# TurntableStrobeModule.net
KiCad netlist of a schematic drawn in EAGLE
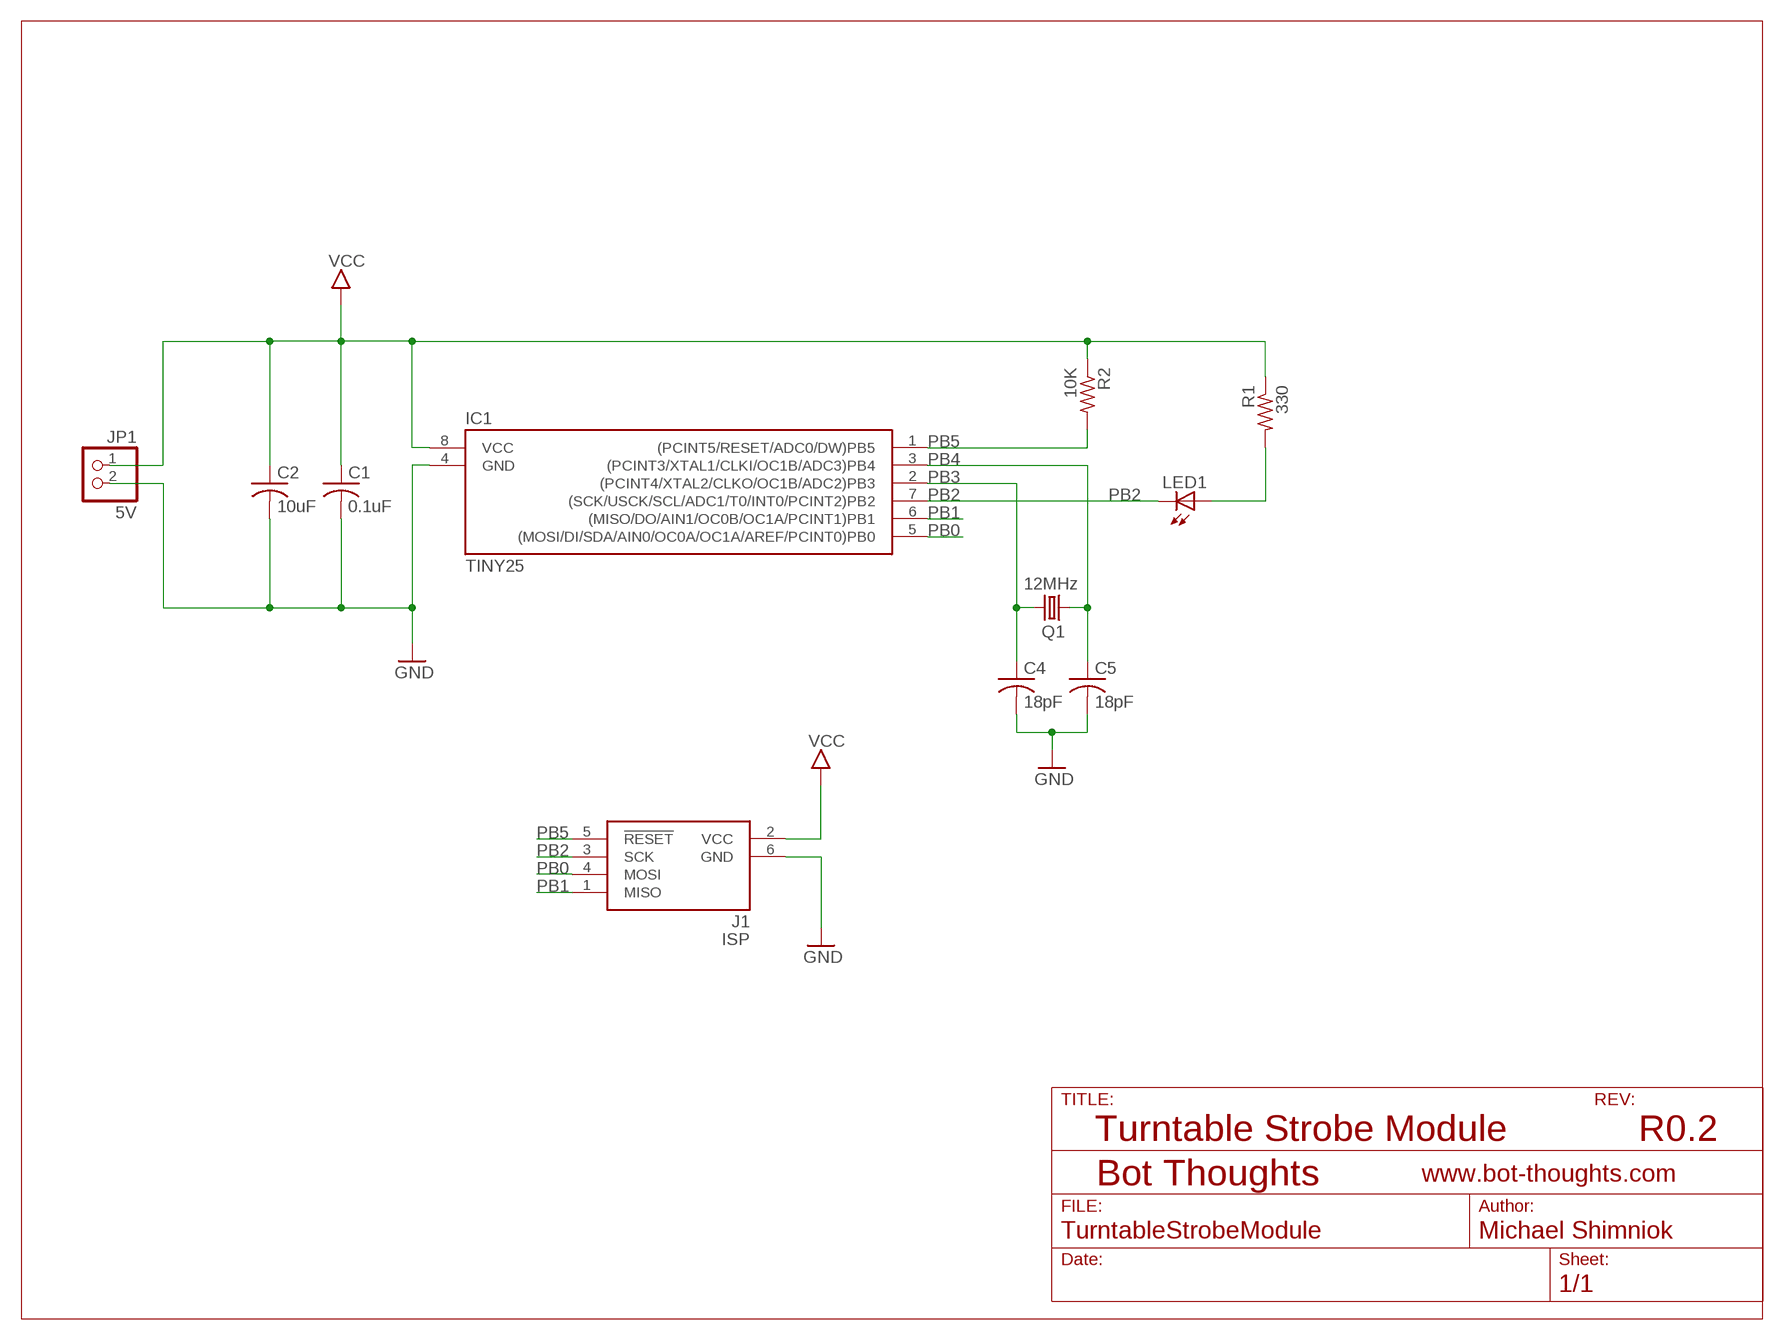
[diagram p0: schematic, sheet 1]

(export (version "E")
  (design (tool "Eeschema 10.0.6"))
  (components
    (comp (ref "C1")
      (value "0.1uF")
      (footprint "eagle-import:C0603")
      (libsource (lib "eagle-import") (part "C-USC0603"))
    )
    (comp (ref "C2")
      (value "10uF")
      (footprint "eagle-import:C1206")
      (libsource (lib "eagle-import") (part "C-USC1206"))
    )
    (comp (ref "C4")
      (value "18pF")
      (footprint "eagle-import:C0603")
      (libsource (lib "eagle-import") (part "C-USC0603"))
    )
    (comp (ref "C5")
      (value "18pF")
      (footprint "eagle-import:C0603")
      (libsource (lib "eagle-import") (part "C-USC0603"))
    )
    (comp (ref "IC1")
      (value "TINY25")
      (footprint "eagle-import:SOIC8N")
      (libsource (lib "eagle-import") (part "TINY25/45/85-20SSU"))
    )
    (comp (ref "J1")
      (value "ISP")
      (footprint "eagle-import:CON6P2R")
      (libsource (lib "eagle-import") (part "AVRISP6_COMPACT"))
    )
    (comp (ref "JP1")
      (value "5V")
      (footprint "eagle-import:1X02-S")
      (libsource (lib "eagle-import") (part "PINHD-1X02_2.54-S"))
    )
    (comp (ref "LED1")
      (value "LED5MMRA")
      (footprint "eagle-import:LED5MMRA")
      (libsource (lib "eagle-import") (part "LED5MMRA"))
    )
    (comp (ref "Q1")
      (value "12MHz")
      (footprint "eagle-import:NDK_2PAD_5X3")
      (libsource (lib "eagle-import") (part "CRYSTALNDK5X3"))
    )
    (comp (ref "R1")
      (value "330")
      (footprint "eagle-import:R0603")
      (libsource (lib "eagle-import") (part "R-US_R0603"))
    )
    (comp (ref "R2")
      (value "10K")
      (footprint "eagle-import:R0603")
      (libsource (lib "eagle-import") (part "R-US_R0603"))
    )
  )
  (nets
    (net (code "1") (name "/PB0") (class "Default")
      (node (ref "IC1") (pin "5") (pinfunction "(MOSI/DI/SDA/AIN0/OC0A/OC1A/AREF/PCINT0)PB0_5") (pintype "bidirectional"))
      (node (ref "J1") (pin "4") (pinfunction "MOSI_4") (pintype "output"))
    )
    (net (code "2") (name "/PB1") (class "Default")
      (node (ref "IC1") (pin "6") (pinfunction "(MISO/DO/AIN1/OC0B/OC1A/PCINT1)PB1_6") (pintype "bidirectional"))
      (node (ref "J1") (pin "1") (pinfunction "MISO_1") (pintype "input"))
    )
    (net (code "3") (name "/PB2") (class "Default")
      (node (ref "IC1") (pin "7") (pinfunction "(SCK/USCK/SCL/ADC1/T0/INT0/PCINT2)PB2_7") (pintype "bidirectional"))
      (node (ref "J1") (pin "3") (pinfunction "SCK_3") (pintype "output"))
      (node (ref "LED1") (pin "C") (pinfunction "C_C") (pintype "passive"))
    )
    (net (code "4") (name "/PB3") (class "Default")
      (node (ref "C4") (pin "1") (pinfunction "1_1") (pintype "passive"))
      (node (ref "IC1") (pin "2") (pinfunction "(PCINT4/XTAL2/CLKO/OC1B/ADC2)PB3_2") (pintype "bidirectional"))
      (node (ref "Q1") (pin "P$2") (pinfunction "2_P$2") (pintype "passive"))
    )
    (net (code "5") (name "/PB4") (class "Default")
      (node (ref "C5") (pin "1") (pinfunction "1_1") (pintype "passive"))
      (node (ref "IC1") (pin "3") (pinfunction "(PCINT3/XTAL1/CLKI/OC1B/ADC3)PB4_3") (pintype "bidirectional"))
      (node (ref "Q1") (pin "P$1") (pinfunction "1_P$1") (pintype "passive"))
    )
    (net (code "6") (name "/PB5") (class "Default")
      (node (ref "IC1") (pin "1") (pinfunction "(PCINT5/RESET/ADC0/DW)PB5_1") (pintype "bidirectional"))
      (node (ref "J1") (pin "5") (pinfunction "~{RESET}_5") (pintype "output"))
      (node (ref "R2") (pin "2") (pinfunction "2_2") (pintype "passive"))
    )
    (net (code "7") (name "GND") (class "Default")
      (node (ref "C1") (pin "2") (pinfunction "2_2") (pintype "passive"))
      (node (ref "C2") (pin "2") (pinfunction "2_2") (pintype "passive"))
      (node (ref "C4") (pin "2") (pinfunction "2_2") (pintype "passive"))
      (node (ref "C5") (pin "2") (pinfunction "2_2") (pintype "passive"))
      (node (ref "IC1") (pin "4") (pinfunction "GND_4") (pintype "power_in"))
      (node (ref "J1") (pin "6") (pinfunction "GND_6") (pintype "power_in"))
      (node (ref "JP1") (pin "2") (pinfunction "2_2") (pintype "passive"))
    )
    (net (code "8") (name "Net-(LED1-PadA)") (class "Default")
      (node (ref "LED1") (pin "A") (pinfunction "A_A") (pintype "passive"))
      (node (ref "R1") (pin "2") (pinfunction "2_2") (pintype "passive"))
    )
    (net (code "9") (name "VCC") (class "Default")
      (node (ref "C1") (pin "1") (pinfunction "1_1") (pintype "passive"))
      (node (ref "C2") (pin "1") (pinfunction "1_1") (pintype "passive"))
      (node (ref "IC1") (pin "8") (pinfunction "VCC_8") (pintype "power_in"))
      (node (ref "J1") (pin "2") (pinfunction "VCC_2") (pintype "power_in"))
      (node (ref "JP1") (pin "1") (pinfunction "1_1") (pintype "passive"))
      (node (ref "R1") (pin "1") (pinfunction "1_1") (pintype "passive"))
      (node (ref "R2") (pin "1") (pinfunction "1_1") (pintype "passive"))
    )
  )
)
